# AD_0.net
KiCad netlist of a schematic drawn in Altium Designer
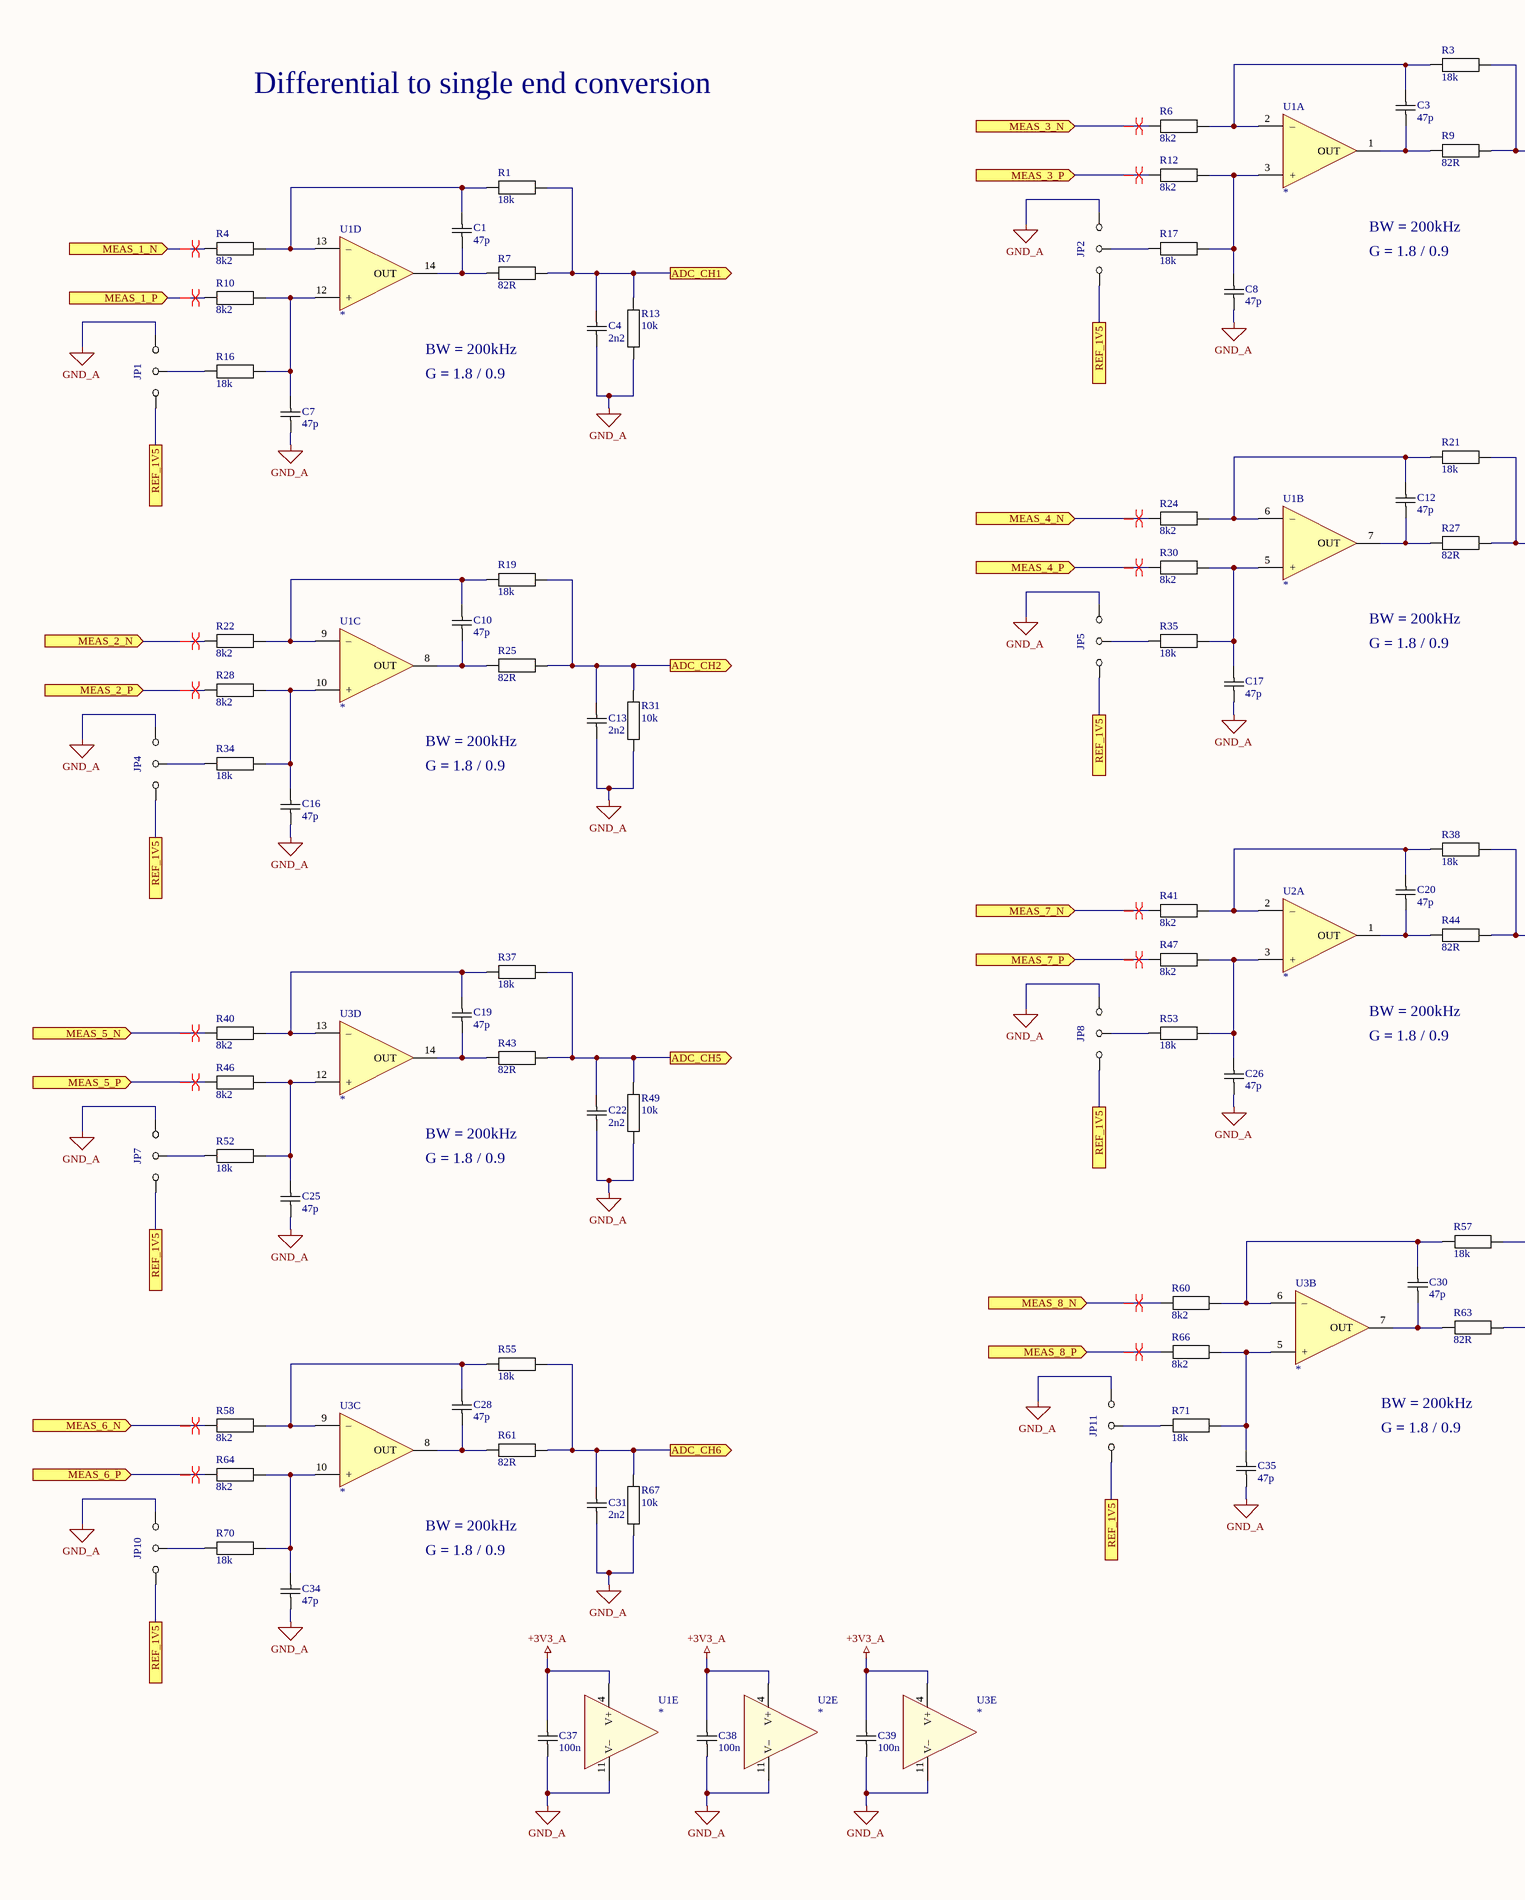
[diagram p0: AD_0.SchDoc, left]
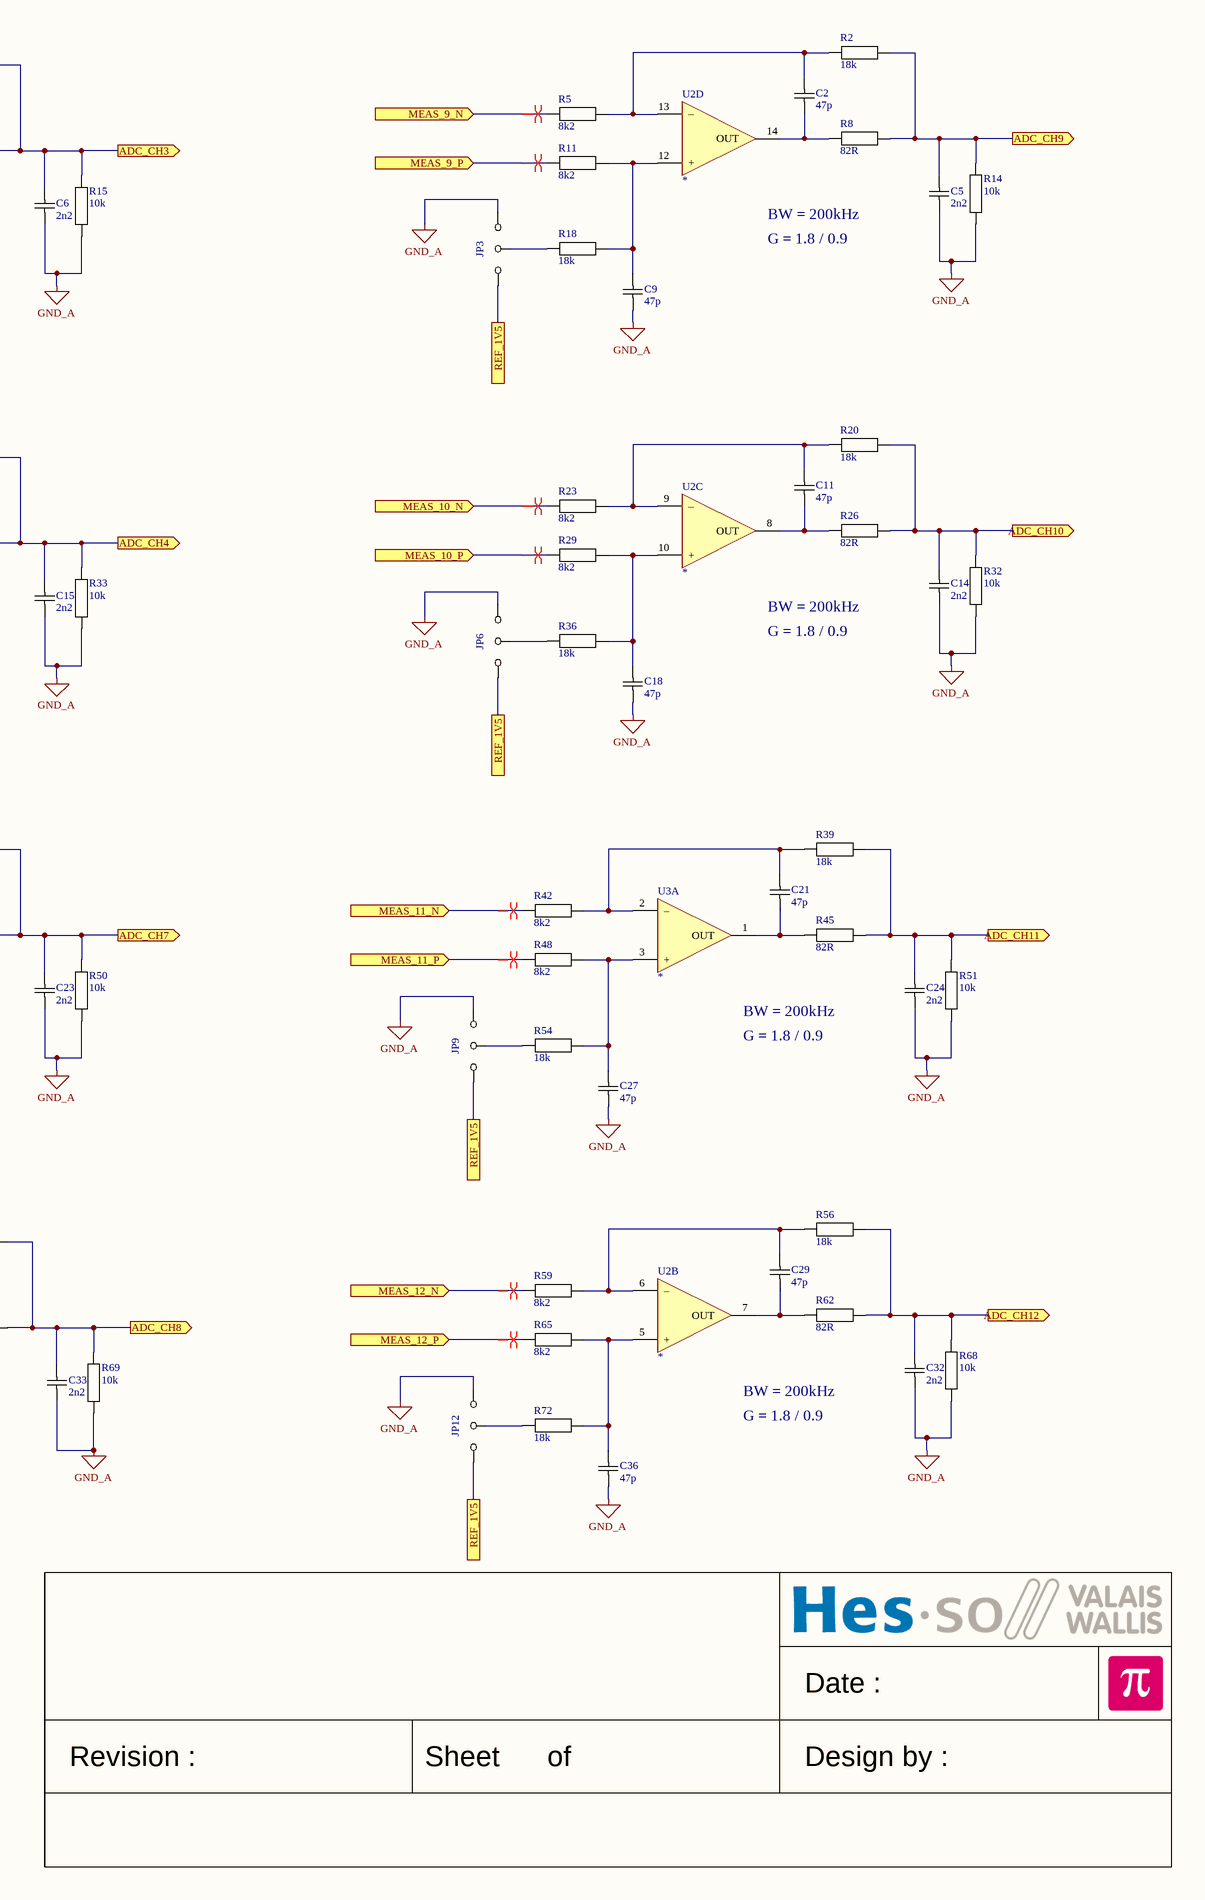
[diagram p1: AD_0.SchDoc, right]

(export (version "E")
  (design (tool "Eeschema 10.0.6"))
  (components
    (comp (ref "C1")
      (value "47p")
      (footprint "CAPACITOR 1608 REFLOW")
      (description "Capacitor X7R 10% 50V 1608(0603)")
      (libsource (lib "Capacitor") (part "Capacitor"))
    )
    (comp (ref "C2")
      (value "47p")
      (footprint "CAPACITOR 1608 REFLOW")
      (description "Capacitor X7R 10% 50V 1608(0603)")
      (libsource (lib "Capacitor") (part "Capacitor"))
    )
    (comp (ref "C3")
      (value "47p")
      (footprint "CAPACITOR 1608 REFLOW")
      (description "Capacitor X7R 10% 50V 1608(0603)")
      (libsource (lib "Capacitor") (part "Capacitor"))
    )
    (comp (ref "C4")
      (value "2n2")
      (footprint "CAPACITOR 1608 REFLOW")
      (description "Capacitor X7R 10% 50V 1608(0603)")
      (libsource (lib "Capacitor") (part "Capacitor"))
    )
    (comp (ref "C5")
      (value "2n2")
      (footprint "CAPACITOR 1608 REFLOW")
      (description "Capacitor X7R 10% 50V 1608(0603)")
      (libsource (lib "Capacitor") (part "Capacitor"))
    )
    (comp (ref "C6")
      (value "2n2")
      (footprint "CAPACITOR 1608 REFLOW")
      (description "Capacitor X7R 10% 50V 1608(0603)")
      (libsource (lib "Capacitor") (part "Capacitor"))
    )
    (comp (ref "C7")
      (value "47p")
      (footprint "CAPACITOR 1608 REFLOW")
      (description "Capacitor X7R 10% 50V 1608(0603)")
      (libsource (lib "Capacitor") (part "Capacitor"))
    )
    (comp (ref "C8")
      (value "47p")
      (footprint "CAPACITOR 1608 REFLOW")
      (description "Capacitor X7R 10% 50V 1608(0603)")
      (libsource (lib "Capacitor") (part "Capacitor"))
    )
    (comp (ref "C9")
      (value "47p")
      (footprint "CAPACITOR 1608 REFLOW")
      (description "Capacitor X7R 10% 50V 1608(0603)")
      (libsource (lib "Capacitor") (part "Capacitor"))
    )
    (comp (ref "C10")
      (value "47p")
      (footprint "CAPACITOR 1608 REFLOW")
      (description "Capacitor X7R 10% 50V 1608(0603)")
      (libsource (lib "Capacitor") (part "Capacitor"))
    )
    (comp (ref "C11")
      (value "47p")
      (footprint "CAPACITOR 1608 REFLOW")
      (description "Capacitor X7R 10% 50V 1608(0603)")
      (libsource (lib "Capacitor") (part "Capacitor"))
    )
    (comp (ref "C12")
      (value "47p")
      (footprint "CAPACITOR 1608 REFLOW")
      (description "Capacitor X7R 10% 50V 1608(0603)")
      (libsource (lib "Capacitor") (part "Capacitor"))
    )
    (comp (ref "C13")
      (value "2n2")
      (footprint "CAPACITOR 1608 REFLOW")
      (description "Capacitor X7R 10% 50V 1608(0603)")
      (libsource (lib "Capacitor") (part "Capacitor"))
    )
    (comp (ref "C14")
      (value "2n2")
      (footprint "CAPACITOR 1608 REFLOW")
      (description "Capacitor X7R 10% 50V 1608(0603)")
      (libsource (lib "Capacitor") (part "Capacitor"))
    )
    (comp (ref "C15")
      (value "2n2")
      (footprint "CAPACITOR 1608 REFLOW")
      (description "Capacitor X7R 10% 50V 1608(0603)")
      (libsource (lib "Capacitor") (part "Capacitor"))
    )
    (comp (ref "C16")
      (value "47p")
      (footprint "CAPACITOR 1608 REFLOW")
      (description "Capacitor X7R 10% 50V 1608(0603)")
      (libsource (lib "Capacitor") (part "Capacitor"))
    )
    (comp (ref "C17")
      (value "47p")
      (footprint "CAPACITOR 1608 REFLOW")
      (description "Capacitor X7R 10% 50V 1608(0603)")
      (libsource (lib "Capacitor") (part "Capacitor"))
    )
    (comp (ref "C18")
      (value "47p")
      (footprint "CAPACITOR 1608 REFLOW")
      (description "Capacitor X7R 10% 50V 1608(0603)")
      (libsource (lib "Capacitor") (part "Capacitor"))
    )
    (comp (ref "C19")
      (value "47p")
      (footprint "CAPACITOR 1608 REFLOW")
      (description "Capacitor X7R 10% 50V 1608(0603)")
      (libsource (lib "Capacitor") (part "Capacitor"))
    )
    (comp (ref "C20")
      (value "47p")
      (footprint "CAPACITOR 1608 REFLOW")
      (description "Capacitor X7R 10% 50V 1608(0603)")
      (libsource (lib "Capacitor") (part "Capacitor"))
    )
    (comp (ref "C21")
      (value "47p")
      (footprint "CAPACITOR 1608 REFLOW")
      (description "Capacitor X7R 10% 50V 1608(0603)")
      (libsource (lib "Capacitor") (part "Capacitor"))
    )
    (comp (ref "C22")
      (value "2n2")
      (footprint "CAPACITOR 1608 REFLOW")
      (description "Capacitor X7R 10% 50V 1608(0603)")
      (libsource (lib "Capacitor") (part "Capacitor"))
    )
    (comp (ref "C23")
      (value "2n2")
      (footprint "CAPACITOR 1608 REFLOW")
      (description "Capacitor X7R 10% 50V 1608(0603)")
      (libsource (lib "Capacitor") (part "Capacitor"))
    )
    (comp (ref "C24")
      (value "2n2")
      (footprint "CAPACITOR 1608 REFLOW")
      (description "Capacitor X7R 10% 50V 1608(0603)")
      (libsource (lib "Capacitor") (part "Capacitor"))
    )
    (comp (ref "C25")
      (value "47p")
      (footprint "CAPACITOR 1608 REFLOW")
      (description "Capacitor X7R 10% 50V 1608(0603)")
      (libsource (lib "Capacitor") (part "Capacitor"))
    )
    (comp (ref "C26")
      (value "47p")
      (footprint "CAPACITOR 1608 REFLOW")
      (description "Capacitor X7R 10% 50V 1608(0603)")
      (libsource (lib "Capacitor") (part "Capacitor"))
    )
    (comp (ref "C27")
      (value "47p")
      (footprint "CAPACITOR 1608 REFLOW")
      (description "Capacitor X7R 10% 50V 1608(0603)")
      (libsource (lib "Capacitor") (part "Capacitor"))
    )
    (comp (ref "C28")
      (value "47p")
      (footprint "CAPACITOR 1608 REFLOW")
      (description "Capacitor X7R 10% 50V 1608(0603)")
      (libsource (lib "Capacitor") (part "Capacitor"))
    )
    (comp (ref "C29")
      (value "47p")
      (footprint "CAPACITOR 1608 REFLOW")
      (description "Capacitor X7R 10% 50V 1608(0603)")
      (libsource (lib "Capacitor") (part "Capacitor"))
    )
    (comp (ref "C30")
      (value "47p")
      (footprint "CAPACITOR 1608 REFLOW")
      (description "Capacitor X7R 10% 50V 1608(0603)")
      (libsource (lib "Capacitor") (part "Capacitor"))
    )
    (comp (ref "C31")
      (value "2n2")
      (footprint "CAPACITOR 1608 REFLOW")
      (description "Capacitor X7R 10% 50V 1608(0603)")
      (libsource (lib "Capacitor") (part "Capacitor"))
    )
    (comp (ref "C32")
      (value "2n2")
      (footprint "CAPACITOR 1608 REFLOW")
      (description "Capacitor X7R 10% 50V 1608(0603)")
      (libsource (lib "Capacitor") (part "Capacitor"))
    )
    (comp (ref "C33")
      (value "2n2")
      (footprint "CAPACITOR 1608 REFLOW")
      (description "Capacitor X7R 10% 50V 1608(0603)")
      (libsource (lib "Capacitor") (part "Capacitor"))
    )
    (comp (ref "C34")
      (value "47p")
      (footprint "CAPACITOR 1608 REFLOW")
      (description "Capacitor X7R 10% 50V 1608(0603)")
      (libsource (lib "Capacitor") (part "Capacitor"))
    )
    (comp (ref "C35")
      (value "47p")
      (footprint "CAPACITOR 1608 REFLOW")
      (description "Capacitor X7R 10% 50V 1608(0603)")
      (libsource (lib "Capacitor") (part "Capacitor"))
    )
    (comp (ref "C36")
      (value "47p")
      (footprint "CAPACITOR 1608 REFLOW")
      (description "Capacitor X7R 10% 50V 1608(0603)")
      (libsource (lib "Capacitor") (part "Capacitor"))
    )
    (comp (ref "C37")
      (value "100n")
      (footprint "CAPACITOR 1608 REFLOW")
      (description "Capacitor X7R 10% 50V 1608(0603)")
      (libsource (lib "Capacitor") (part "Capacitor"))
    )
    (comp (ref "C38")
      (value "100n")
      (footprint "CAPACITOR 1608 REFLOW")
      (description "Capacitor X7R 10% 50V 1608(0603)")
      (libsource (lib "Capacitor") (part "Capacitor"))
    )
    (comp (ref "C39")
      (value "100n")
      (footprint "CAPACITOR 1608 REFLOW")
      (description "Capacitor X7R 10% 50V 1608(0603)")
      (libsource (lib "Capacitor") (part "Capacitor"))
    )
    (comp (ref "JP1")
      (value "{Value}")
      (footprint "JUMPER3 SMD 1608")
      (description "JUMPER 3 POS")
      (libsource (lib "Jumper") (part "JUMPER 3 POS"))
    )
    (comp (ref "JP2")
      (value "{Value}")
      (footprint "JUMPER3 SMD 1608")
      (description "JUMPER 3 POS")
      (libsource (lib "Jumper") (part "JUMPER 3 POS"))
    )
    (comp (ref "JP3")
      (value "{Value}")
      (footprint "JUMPER3 SMD 1608")
      (description "JUMPER 3 POS")
      (libsource (lib "Jumper") (part "JUMPER 3 POS"))
    )
    (comp (ref "JP4")
      (value "{Value}")
      (footprint "JUMPER3 SMD 1608")
      (description "JUMPER 3 POS")
      (libsource (lib "Jumper") (part "JUMPER 3 POS"))
    )
    (comp (ref "JP5")
      (value "{Value}")
      (footprint "JUMPER3 SMD 1608")
      (description "JUMPER 3 POS")
      (libsource (lib "Jumper") (part "JUMPER 3 POS"))
    )
    (comp (ref "JP6")
      (value "{Value}")
      (footprint "JUMPER3 SMD 1608")
      (description "JUMPER 3 POS")
      (libsource (lib "Jumper") (part "JUMPER 3 POS"))
    )
    (comp (ref "JP7")
      (value "{Value}")
      (footprint "JUMPER3 SMD 1608")
      (description "JUMPER 3 POS")
      (libsource (lib "Jumper") (part "JUMPER 3 POS"))
    )
    (comp (ref "JP8")
      (value "{Value}")
      (footprint "JUMPER3 SMD 1608")
      (description "JUMPER 3 POS")
      (libsource (lib "Jumper") (part "JUMPER 3 POS"))
    )
    (comp (ref "JP9")
      (value "{Value}")
      (footprint "JUMPER3 SMD 1608")
      (description "JUMPER 3 POS")
      (libsource (lib "Jumper") (part "JUMPER 3 POS"))
    )
    (comp (ref "JP10")
      (value "{Value}")
      (footprint "JUMPER3 SMD 1608")
      (description "JUMPER 3 POS")
      (libsource (lib "Jumper") (part "JUMPER 3 POS"))
    )
    (comp (ref "JP11")
      (value "{Value}")
      (footprint "JUMPER3 SMD 1608")
      (description "JUMPER 3 POS")
      (libsource (lib "Jumper") (part "JUMPER 3 POS"))
    )
    (comp (ref "JP12")
      (value "{Value}")
      (footprint "JUMPER3 SMD 1608")
      (description "JUMPER 3 POS")
      (libsource (lib "Jumper") (part "JUMPER 3 POS"))
    )
    (comp (ref "R1")
      (value "18k")
      (footprint "RESISTOR 1608 REFLOW")
      (description "Resistor 1% 50V 100mW 1608(0603)")
      (libsource (lib "Resistor") (part "Resistor"))
    )
    (comp (ref "R2")
      (value "18k")
      (footprint "RESISTOR 1608 REFLOW")
      (description "Resistor 1% 50V 100mW 1608(0603)")
      (libsource (lib "Resistor") (part "Resistor"))
    )
    (comp (ref "R3")
      (value "18k")
      (footprint "RESISTOR 1608 REFLOW")
      (description "Resistor 1% 50V 100mW 1608(0603)")
      (libsource (lib "Resistor") (part "Resistor"))
    )
    (comp (ref "R4")
      (value "8k2")
      (footprint "RESISTOR 1608 REFLOW")
      (description "Resistor 1% 50V 100mW 1608(0603)")
      (libsource (lib "Resistor") (part "Resistor"))
    )
    (comp (ref "R5")
      (value "8k2")
      (footprint "RESISTOR 1608 REFLOW")
      (description "Resistor 1% 50V 100mW 1608(0603)")
      (libsource (lib "Resistor") (part "Resistor"))
    )
    (comp (ref "R6")
      (value "8k2")
      (footprint "RESISTOR 1608 REFLOW")
      (description "Resistor 1% 50V 100mW 1608(0603)")
      (libsource (lib "Resistor") (part "Resistor"))
    )
    (comp (ref "R7")
      (value "82R")
      (footprint "RESISTOR 1608 REFLOW")
      (description "Resistor 1% 50V 100mW 1608(0603)")
      (libsource (lib "Resistor") (part "Resistor"))
    )
    (comp (ref "R8")
      (value "82R")
      (footprint "RESISTOR 1608 REFLOW")
      (description "Resistor 1% 50V 100mW 1608(0603)")
      (libsource (lib "Resistor") (part "Resistor"))
    )
    (comp (ref "R9")
      (value "82R")
      (footprint "RESISTOR 1608 REFLOW")
      (description "Resistor 1% 50V 100mW 1608(0603)")
      (libsource (lib "Resistor") (part "Resistor"))
    )
    (comp (ref "R10")
      (value "8k2")
      (footprint "RESISTOR 1608 REFLOW")
      (description "Resistor 1% 50V 100mW 1608(0603)")
      (libsource (lib "Resistor") (part "Resistor"))
    )
    (comp (ref "R11")
      (value "8k2")
      (footprint "RESISTOR 1608 REFLOW")
      (description "Resistor 1% 50V 100mW 1608(0603)")
      (libsource (lib "Resistor") (part "Resistor"))
    )
    (comp (ref "R12")
      (value "8k2")
      (footprint "RESISTOR 1608 REFLOW")
      (description "Resistor 1% 50V 100mW 1608(0603)")
      (libsource (lib "Resistor") (part "Resistor"))
    )
    (comp (ref "R13")
      (value "10k")
      (footprint "RESISTOR 1608 REFLOW")
      (description "Resistor 1% 50V 100mW 1608(0603)")
      (libsource (lib "Resistor") (part "Resistor"))
    )
    (comp (ref "R14")
      (value "10k")
      (footprint "RESISTOR 1608 REFLOW")
      (description "Resistor 1% 50V 100mW 1608(0603)")
      (libsource (lib "Resistor") (part "Resistor"))
    )
    (comp (ref "R15")
      (value "10k")
      (footprint "RESISTOR 1608 REFLOW")
      (description "Resistor 1% 50V 100mW 1608(0603)")
      (libsource (lib "Resistor") (part "Resistor"))
    )
    (comp (ref "R16")
      (value "18k")
      (footprint "RESISTOR 1608 REFLOW")
      (description "Resistor 1% 50V 100mW 1608(0603)")
      (libsource (lib "Resistor") (part "Resistor"))
    )
    (comp (ref "R17")
      (value "18k")
      (footprint "RESISTOR 1608 REFLOW")
      (description "Resistor 1% 50V 100mW 1608(0603)")
      (libsource (lib "Resistor") (part "Resistor"))
    )
    (comp (ref "R18")
      (value "18k")
      (footprint "RESISTOR 1608 REFLOW")
      (description "Resistor 1% 50V 100mW 1608(0603)")
      (libsource (lib "Resistor") (part "Resistor"))
    )
    (comp (ref "R19")
      (value "18k")
      (footprint "RESISTOR 1608 REFLOW")
      (description "Resistor 1% 50V 100mW 1608(0603)")
      (libsource (lib "Resistor") (part "Resistor"))
    )
    (comp (ref "R20")
      (value "18k")
      (footprint "RESISTOR 1608 REFLOW")
      (description "Resistor 1% 50V 100mW 1608(0603)")
      (libsource (lib "Resistor") (part "Resistor"))
    )
    (comp (ref "R21")
      (value "18k")
      (footprint "RESISTOR 1608 REFLOW")
      (description "Resistor 1% 50V 100mW 1608(0603)")
      (libsource (lib "Resistor") (part "Resistor"))
    )
    (comp (ref "R22")
      (value "8k2")
      (footprint "RESISTOR 1608 REFLOW")
      (description "Resistor 1% 50V 100mW 1608(0603)")
      (libsource (lib "Resistor") (part "Resistor"))
    )
    (comp (ref "R23")
      (value "8k2")
      (footprint "RESISTOR 1608 REFLOW")
      (description "Resistor 1% 50V 100mW 1608(0603)")
      (libsource (lib "Resistor") (part "Resistor"))
    )
    (comp (ref "R24")
      (value "8k2")
      (footprint "RESISTOR 1608 REFLOW")
      (description "Resistor 1% 50V 100mW 1608(0603)")
      (libsource (lib "Resistor") (part "Resistor"))
    )
    (comp (ref "R25")
      (value "82R")
      (footprint "RESISTOR 1608 REFLOW")
      (description "Resistor 1% 50V 100mW 1608(0603)")
      (libsource (lib "Resistor") (part "Resistor"))
    )
    (comp (ref "R26")
      (value "82R")
      (footprint "RESISTOR 1608 REFLOW")
      (description "Resistor 1% 50V 100mW 1608(0603)")
      (libsource (lib "Resistor") (part "Resistor"))
    )
    (comp (ref "R27")
      (value "82R")
      (footprint "RESISTOR 1608 REFLOW")
      (description "Resistor 1% 50V 100mW 1608(0603)")
      (libsource (lib "Resistor") (part "Resistor"))
    )
    (comp (ref "R28")
      (value "8k2")
      (footprint "RESISTOR 1608 REFLOW")
      (description "Resistor 1% 50V 100mW 1608(0603)")
      (libsource (lib "Resistor") (part "Resistor"))
    )
    (comp (ref "R29")
      (value "8k2")
      (footprint "RESISTOR 1608 REFLOW")
      (description "Resistor 1% 50V 100mW 1608(0603)")
      (libsource (lib "Resistor") (part "Resistor"))
    )
    (comp (ref "R30")
      (value "8k2")
      (footprint "RESISTOR 1608 REFLOW")
      (description "Resistor 1% 50V 100mW 1608(0603)")
      (libsource (lib "Resistor") (part "Resistor"))
    )
    (comp (ref "R31")
      (value "10k")
      (footprint "RESISTOR 1608 REFLOW")
      (description "Resistor 1% 50V 100mW 1608(0603)")
      (libsource (lib "Resistor") (part "Resistor"))
    )
    (comp (ref "R32")
      (value "10k")
      (footprint "RESISTOR 1608 REFLOW")
      (description "Resistor 1% 50V 100mW 1608(0603)")
      (libsource (lib "Resistor") (part "Resistor"))
    )
    (comp (ref "R33")
      (value "10k")
      (footprint "RESISTOR 1608 REFLOW")
      (description "Resistor 1% 50V 100mW 1608(0603)")
      (libsource (lib "Resistor") (part "Resistor"))
    )
    (comp (ref "R34")
      (value "18k")
      (footprint "RESISTOR 1608 REFLOW")
      (description "Resistor 1% 50V 100mW 1608(0603)")
      (libsource (lib "Resistor") (part "Resistor"))
    )
    (comp (ref "R35")
      (value "18k")
      (footprint "RESISTOR 1608 REFLOW")
      (description "Resistor 1% 50V 100mW 1608(0603)")
      (libsource (lib "Resistor") (part "Resistor"))
    )
    (comp (ref "R36")
      (value "18k")
      (footprint "RESISTOR 1608 REFLOW")
      (description "Resistor 1% 50V 100mW 1608(0603)")
      (libsource (lib "Resistor") (part "Resistor"))
    )
    (comp (ref "R37")
      (value "18k")
      (footprint "RESISTOR 1608 REFLOW")
      (description "Resistor 1% 50V 100mW 1608(0603)")
      (libsource (lib "Resistor") (part "Resistor"))
    )
    (comp (ref "R38")
      (value "18k")
      (footprint "RESISTOR 1608 REFLOW")
      (description "Resistor 1% 50V 100mW 1608(0603)")
      (libsource (lib "Resistor") (part "Resistor"))
    )
    (comp (ref "R39")
      (value "18k")
      (footprint "RESISTOR 1608 REFLOW")
      (description "Resistor 1% 50V 100mW 1608(0603)")
      (libsource (lib "Resistor") (part "Resistor"))
    )
    (comp (ref "R40")
      (value "8k2")
      (footprint "RESISTOR 1608 REFLOW")
      (description "Resistor 1% 50V 100mW 1608(0603)")
      (libsource (lib "Resistor") (part "Resistor"))
    )
    (comp (ref "R41")
      (value "8k2")
      (footprint "RESISTOR 1608 REFLOW")
      (description "Resistor 1% 50V 100mW 1608(0603)")
      (libsource (lib "Resistor") (part "Resistor"))
    )
    (comp (ref "R42")
      (value "8k2")
      (footprint "RESISTOR 1608 REFLOW")
      (description "Resistor 1% 50V 100mW 1608(0603)")
      (libsource (lib "Resistor") (part "Resistor"))
    )
    (comp (ref "R43")
      (value "82R")
      (footprint "RESISTOR 1608 REFLOW")
      (description "Resistor 1% 50V 100mW 1608(0603)")
      (libsource (lib "Resistor") (part "Resistor"))
    )
    (comp (ref "R44")
      (value "82R")
      (footprint "RESISTOR 1608 REFLOW")
      (description "Resistor 1% 50V 100mW 1608(0603)")
      (libsource (lib "Resistor") (part "Resistor"))
    )
    (comp (ref "R45")
      (value "82R")
      (footprint "RESISTOR 1608 REFLOW")
      (description "Resistor 1% 50V 100mW 1608(0603)")
      (libsource (lib "Resistor") (part "Resistor"))
    )
    (comp (ref "R46")
      (value "8k2")
      (footprint "RESISTOR 1608 REFLOW")
      (description "Resistor 1% 50V 100mW 1608(0603)")
      (libsource (lib "Resistor") (part "Resistor"))
    )
    (comp (ref "R47")
      (value "8k2")
      (footprint "RESISTOR 1608 REFLOW")
      (description "Resistor 1% 50V 100mW 1608(0603)")
      (libsource (lib "Resistor") (part "Resistor"))
    )
    (comp (ref "R48")
      (value "8k2")
      (footprint "RESISTOR 1608 REFLOW")
      (description "Resistor 1% 50V 100mW 1608(0603)")
      (libsource (lib "Resistor") (part "Resistor"))
    )
    (comp (ref "R49")
      (value "10k")
      (footprint "RESISTOR 1608 REFLOW")
      (description "Resistor 1% 50V 100mW 1608(0603)")
      (libsource (lib "Resistor") (part "Resistor"))
    )
    (comp (ref "R50")
      (value "10k")
      (footprint "RESISTOR 1608 REFLOW")
      (description "Resistor 1% 50V 100mW 1608(0603)")
      (libsource (lib "Resistor") (part "Resistor"))
    )
    (comp (ref "R51")
      (value "10k")
      (footprint "RESISTOR 1608 REFLOW")
      (description "Resistor 1% 50V 100mW 1608(0603)")
      (libsource (lib "Resistor") (part "Resistor"))
    )
    (comp (ref "R52")
      (value "18k")
      (footprint "RESISTOR 1608 REFLOW")
      (description "Resistor 1% 50V 100mW 1608(0603)")
      (libsource (lib "Resistor") (part "Resistor"))
    )
    (comp (ref "R53")
      (value "18k")
      (footprint "RESISTOR 1608 REFLOW")
      (description "Resistor 1% 50V 100mW 1608(0603)")
      (libsource (lib "Resistor") (part "Resistor"))
    )
    (comp (ref "R54")
      (value "18k")
      (footprint "RESISTOR 1608 REFLOW")
      (description "Resistor 1% 50V 100mW 1608(0603)")
      (libsource (lib "Resistor") (part "Resistor"))
    )
    (comp (ref "R55")
      (value "18k")
      (footprint "RESISTOR 1608 REFLOW")
      (description "Resistor 1% 50V 100mW 1608(0603)")
      (libsource (lib "Resistor") (part "Resistor"))
    )
    (comp (ref "R56")
      (value "18k")
      (footprint "RESISTOR 1608 REFLOW")
      (description "Resistor 1% 50V 100mW 1608(0603)")
      (libsource (lib "Resistor") (part "Resistor"))
    )
    (comp (ref "R57")
      (value "18k")
      (footprint "RESISTOR 1608 REFLOW")
      (description "Resistor 1% 50V 100mW 1608(0603)")
      (libsource (lib "Resistor") (part "Resistor"))
    )
    (comp (ref "R58")
      (value "8k2")
      (footprint "RESISTOR 1608 REFLOW")
      (description "Resistor 1% 50V 100mW 1608(0603)")
      (libsource (lib "Resistor") (part "Resistor"))
    )
    (comp (ref "R59")
      (value "8k2")
      (footprint "RESISTOR 1608 REFLOW")
      (description "Resistor 1% 50V 100mW 1608(0603)")
      (libsource (lib "Resistor") (part "Resistor"))
    )
    (comp (ref "R60")
      (value "8k2")
      (footprint "RESISTOR 1608 REFLOW")
      (description "Resistor 1% 50V 100mW 1608(0603)")
      (libsource (lib "Resistor") (part "Resistor"))
    )
    (comp (ref "R61")
      (value "82R")
      (footprint "RESISTOR 1608 REFLOW")
      (description "Resistor 1% 50V 100mW 1608(0603)")
      (libsource (lib "Resistor") (part "Resistor"))
    )
    (comp (ref "R62")
      (value "82R")
      (footprint "RESISTOR 1608 REFLOW")
      (description "Resistor 1% 50V 100mW 1608(0603)")
      (libsource (lib "Resistor") (part "Resistor"))
    )
    (comp (ref "R63")
      (value "82R")
      (footprint "RESISTOR 1608 REFLOW")
      (description "Resistor 1% 50V 100mW 1608(0603)")
      (libsource (lib "Resistor") (part "Resistor"))
    )
    (comp (ref "R64")
      (value "8k2")
      (footprint "RESISTOR 1608 REFLOW")
      (description "Resistor 1% 50V 100mW 1608(0603)")
      (libsource (lib "Resistor") (part "Resistor"))
    )
    (comp (ref "R65")
      (value "8k2")
      (footprint "RESISTOR 1608 REFLOW")
      (description "Resistor 1% 50V 100mW 1608(0603)")
      (libsource (lib "Resistor") (part "Resistor"))
    )
    (comp (ref "R66")
      (value "8k2")
      (footprint "RESISTOR 1608 REFLOW")
      (description "Resistor 1% 50V 100mW 1608(0603)")
      (libsource (lib "Resistor") (part "Resistor"))
    )
    (comp (ref "R67")
      (value "10k")
      (footprint "RESISTOR 1608 REFLOW")
      (description "Resistor 1% 50V 100mW 1608(0603)")
      (libsource (lib "Resistor") (part "Resistor"))
    )
    (comp (ref "R68")
      (value "10k")
      (footprint "RESISTOR 1608 REFLOW")
      (description "Resistor 1% 50V 100mW 1608(0603)")
      (libsource (lib "Resistor") (part "Resistor"))
    )
    (comp (ref "R69")
      (value "10k")
      (footprint "RESISTOR 1608 REFLOW")
      (description "Resistor 1% 50V 100mW 1608(0603)")
      (libsource (lib "Resistor") (part "Resistor"))
    )
    (comp (ref "R70")
      (value "18k")
      (footprint "RESISTOR 1608 REFLOW")
      (description "Resistor 1% 50V 100mW 1608(0603)")
      (libsource (lib "Resistor") (part "Resistor"))
    )
    (comp (ref "R71")
      (value "18k")
      (footprint "RESISTOR 1608 REFLOW")
      (description "Resistor 1% 50V 100mW 1608(0603)")
      (libsource (lib "Resistor") (part "Resistor"))
    )
    (comp (ref "R72")
      (value "18k")
      (footprint "RESISTOR 1608 REFLOW")
      (description "Resistor 1% 50V 100mW 1608(0603)")
      (libsource (lib "Resistor") (part "Resistor"))
    )
    (comp (ref "U1")
      (value "*")
      (footprint "SO14 P1.27 C4.0X8.8 H1.75")
      (description "Generic quad OPA 14 pins")
      (libsource (lib "Amplifier") (part "OPA QUAD"))
    )
    (comp (ref "U2")
      (value "*")
      (footprint "SO14 P1.27 C4.0X8.8 H1.75")
      (description "Generic quad OPA 14 pins")
      (libsource (lib "Amplifier") (part "OPA QUAD"))
    )
    (comp (ref "U3")
      (value "*")
      (footprint "SO14 P1.27 C4.0X8.8 H1.75")
      (description "Generic quad OPA 14 pins")
      (libsource (lib "Amplifier") (part "OPA QUAD"))
    )
  )
  (nets
    (net (code "1") (name "+3V3_A") (class "Default")
      (node (ref "C37") (pin "2") (pinfunction "2_2") (pintype "passive"))
      (node (ref "C38") (pin "2") (pinfunction "2_2") (pintype "passive"))
      (node (ref "C39") (pin "2") (pinfunction "2_2") (pintype "passive"))
      (node (ref "U1") (pin "4") (pinfunction "V+_4") (pintype "passive"))
      (node (ref "U2") (pin "4") (pinfunction "V+_4") (pintype "passive"))
      (node (ref "U3") (pin "4") (pinfunction "V+_4") (pintype "passive"))
    )
    (net (code "2") (name "/ADC_CH1") (class "Default")
      (node (ref "C4") (pin "2") (pinfunction "2_2") (pintype "passive"))
      (node (ref "R1") (pin "2") (pinfunction "2_2") (pintype "passive"))
      (node (ref "R13") (pin "1") (pinfunction "1_1") (pintype "passive"))
      (node (ref "R7") (pin "2") (pinfunction "2_2") (pintype "passive"))
    )
    (net (code "3") (name "/ADC_CH2") (class "Default")
      (node (ref "C13") (pin "2") (pinfunction "2_2") (pintype "passive"))
      (node (ref "R19") (pin "2") (pinfunction "2_2") (pintype "passive"))
      (node (ref "R25") (pin "2") (pinfunction "2_2") (pintype "passive"))
      (node (ref "R31") (pin "1") (pinfunction "1_1") (pintype "passive"))
    )
    (net (code "4") (name "/ADC_CH3") (class "Default")
      (node (ref "C6") (pin "2") (pinfunction "2_2") (pintype "passive"))
      (node (ref "R15") (pin "1") (pinfunction "1_1") (pintype "passive"))
      (node (ref "R3") (pin "2") (pinfunction "2_2") (pintype "passive"))
      (node (ref "R9") (pin "2") (pinfunction "2_2") (pintype "passive"))
    )
    (net (code "5") (name "/ADC_CH4") (class "Default")
      (node (ref "C15") (pin "2") (pinfunction "2_2") (pintype "passive"))
      (node (ref "R21") (pin "2") (pinfunction "2_2") (pintype "passive"))
      (node (ref "R27") (pin "2") (pinfunction "2_2") (pintype "passive"))
      (node (ref "R33") (pin "1") (pinfunction "1_1") (pintype "passive"))
    )
    (net (code "6") (name "/ADC_CH5") (class "Default")
      (node (ref "C22") (pin "2") (pinfunction "2_2") (pintype "passive"))
      (node (ref "R37") (pin "2") (pinfunction "2_2") (pintype "passive"))
      (node (ref "R43") (pin "2") (pinfunction "2_2") (pintype "passive"))
      (node (ref "R49") (pin "1") (pinfunction "1_1") (pintype "passive"))
    )
    (net (code "7") (name "/ADC_CH6") (class "Default")
      (node (ref "C31") (pin "2") (pinfunction "2_2") (pintype "passive"))
      (node (ref "R55") (pin "2") (pinfunction "2_2") (pintype "passive"))
      (node (ref "R61") (pin "2") (pinfunction "2_2") (pintype "passive"))
      (node (ref "R67") (pin "1") (pinfunction "1_1") (pintype "passive"))
    )
    (net (code "8") (name "/ADC_CH7") (class "Default")
      (node (ref "C23") (pin "2") (pinfunction "2_2") (pintype "passive"))
      (node (ref "R38") (pin "2") (pinfunction "2_2") (pintype "passive"))
      (node (ref "R44") (pin "2") (pinfunction "2_2") (pintype "passive"))
      (node (ref "R50") (pin "1") (pinfunction "1_1") (pintype "passive"))
    )
    (net (code "9") (name "/ADC_CH8") (class "Default")
      (node (ref "C33") (pin "2") (pinfunction "2_2") (pintype "passive"))
      (node (ref "R57") (pin "2") (pinfunction "2_2") (pintype "passive"))
      (node (ref "R63") (pin "2") (pinfunction "2_2") (pintype "passive"))
      (node (ref "R69") (pin "1") (pinfunction "1_1") (pintype "passive"))
    )
    (net (code "10") (name "/ADC_CH9") (class "Default")
      (node (ref "C5") (pin "2") (pinfunction "2_2") (pintype "passive"))
      (node (ref "R14") (pin "1") (pinfunction "1_1") (pintype "passive"))
      (node (ref "R2") (pin "2") (pinfunction "2_2") (pintype "passive"))
      (node (ref "R8") (pin "2") (pinfunction "2_2") (pintype "passive"))
    )
    (net (code "11") (name "/ADC_CH10") (class "Default")
      (node (ref "C14") (pin "2") (pinfunction "2_2") (pintype "passive"))
      (node (ref "R20") (pin "2") (pinfunction "2_2") (pintype "passive"))
      (node (ref "R26") (pin "2") (pinfunction "2_2") (pintype "passive"))
      (node (ref "R32") (pin "1") (pinfunction "1_1") (pintype "passive"))
    )
    (net (code "12") (name "/ADC_CH11") (class "Default")
      (node (ref "C24") (pin "2") (pinfunction "2_2") (pintype "passive"))
      (node (ref "R39") (pin "2") (pinfunction "2_2") (pintype "passive"))
      (node (ref "R45") (pin "2") (pinfunction "2_2") (pintype "passive"))
      (node (ref "R51") (pin "1") (pinfunction "1_1") (pintype "passive"))
    )
    (net (code "13") (name "/ADC_CH12") (class "Default")
      (node (ref "C32") (pin "2") (pinfunction "2_2") (pintype "passive"))
      (node (ref "R56") (pin "2") (pinfunction "2_2") (pintype "passive"))
      (node (ref "R62") (pin "2") (pinfunction "2_2") (pintype "passive"))
      (node (ref "R68") (pin "1") (pinfunction "1_1") (pintype "passive"))
    )
    (net (code "14") (name "/MEAS_1_N") (class "Default")
      (node (ref "R4") (pin "1") (pinfunction "1_1") (pintype "passive"))
    )
    (net (code "15") (name "/MEAS_1_P") (class "Default")
      (node (ref "R10") (pin "1") (pinfunction "1_1") (pintype "passive"))
    )
    (net (code "16") (name "/MEAS_2_N") (class "Default")
      (node (ref "R22") (pin "1") (pinfunction "1_1") (pintype "passive"))
    )
    (net (code "17") (name "/MEAS_2_P") (class "Default")
      (node (ref "R28") (pin "1") (pinfunction "1_1") (pintype "passive"))
    )
    (net (code "18") (name "/MEAS_3_N") (class "Default")
      (node (ref "R6") (pin "1") (pinfunction "1_1") (pintype "passive"))
    )
    (net (code "19") (name "/MEAS_3_P") (class "Default")
      (node (ref "R12") (pin "1") (pinfunction "1_1") (pintype "passive"))
    )
    (net (code "20") (name "/MEAS_4_N") (class "Default")
      (node (ref "R24") (pin "1") (pinfunction "1_1") (pintype "passive"))
    )
    (net (code "21") (name "/MEAS_4_P") (class "Default")
      (node (ref "R30") (pin "1") (pinfunction "1_1") (pintype "passive"))
    )
    (net (code "22") (name "/MEAS_5_N") (class "Default")
      (node (ref "R40") (pin "1") (pinfunction "1_1") (pintype "passive"))
    )
    (net (code "23") (name "/MEAS_5_P") (class "Default")
      (node (ref "R46") (pin "1") (pinfunction "1_1") (pintype "passive"))
    )
    (net (code "24") (name "/MEAS_6_N") (class "Default")
      (node (ref "R58") (pin "1") (pinfunction "1_1") (pintype "passive"))
    )
    (net (code "25") (name "/MEAS_6_P") (class "Default")
      (node (ref "R64") (pin "1") (pinfunction "1_1") (pintype "passive"))
    )
    (net (code "26") (name "/MEAS_7_N") (class "Default")
      (node (ref "R41") (pin "1") (pinfunction "1_1") (pintype "passive"))
    )
    (net (code "27") (name "/MEAS_7_P") (class "Default")
      (node (ref "R47") (pin "1") (pinfunction "1_1") (pintype "passive"))
    )
    (net (code "28") (name "/MEAS_8_N") (class "Default")
      (node (ref "R60") (pin "1") (pinfunction "1_1") (pintype "passive"))
    )
    (net (code "29") (name "/MEAS_8_P") (class "Default")
      (node (ref "R66") (pin "1") (pinfunction "1_1") (pintype "passive"))
    )
    (net (code "30") (name "/MEAS_9_N") (class "Default")
      (node (ref "R5") (pin "1") (pinfunction "1_1") (pintype "passive"))
    )
    (net (code "31") (name "/MEAS_9_P") (class "Default")
      (node (ref "R11") (pin "1") (pinfunction "1_1") (pintype "passive"))
    )
    (net (code "32") (name "/MEAS_10_N") (class "Default")
      (node (ref "R23") (pin "1") (pinfunction "1_1") (pintype "passive"))
    )
    (net (code "33") (name "/MEAS_10_P") (class "Default")
      (node (ref "R29") (pin "1") (pinfunction "1_1") (pintype "passive"))
    )
    (net (code "34") (name "/MEAS_11_N") (class "Default")
      (node (ref "R42") (pin "1") (pinfunction "1_1") (pintype "passive"))
    )
    (net (code "35") (name "/MEAS_11_P") (class "Default")
      (node (ref "R48") (pin "1") (pinfunction "1_1") (pintype "passive"))
    )
    (net (code "36") (name "/MEAS_12_N") (class "Default")
      (node (ref "R59") (pin "1") (pinfunction "1_1") (pintype "passive"))
    )
    (net (code "37") (name "/MEAS_12_P") (class "Default")
      (node (ref "R65") (pin "1") (pinfunction "1_1") (pintype "passive"))
    )
    (net (code "38") (name "/REF_1V5") (class "Default")
      (node (ref "JP1") (pin "1") (pinfunction "1_1") (pintype "passive"))
      (node (ref "JP10") (pin "1") (pinfunction "1_1") (pintype "passive"))
      (node (ref "JP11") (pin "1") (pinfunction "1_1") (pintype "passive"))
      (node (ref "JP12") (pin "1") (pinfunction "1_1") (pintype "passive"))
      (node (ref "JP2") (pin "1") (pinfunction "1_1") (pintype "passive"))
      (node (ref "JP3") (pin "1") (pinfunction "1_1") (pintype "passive"))
      (node (ref "JP4") (pin "1") (pinfunction "1_1") (pintype "passive"))
      (node (ref "JP5") (pin "1") (pinfunction "1_1") (pintype "passive"))
      (node (ref "JP6") (pin "1") (pinfunction "1_1") (pintype "passive"))
      (node (ref "JP7") (pin "1") (pinfunction "1_1") (pintype "passive"))
      (node (ref "JP8") (pin "1") (pinfunction "1_1") (pintype "passive"))
      (node (ref "JP9") (pin "1") (pinfunction "1_1") (pintype "passive"))
    )
    (net (code "39") (name "GND_A") (class "Default")
      (node (ref "C13") (pin "1") (pinfunction "1_1") (pintype "passive"))
      (node (ref "C14") (pin "1") (pinfunction "1_1") (pintype "passive"))
      (node (ref "C15") (pin "1") (pinfunction "1_1") (pintype "passive"))
      (node (ref "C16") (pin "1") (pinfunction "1_1") (pintype "passive"))
      (node (ref "C17") (pin "1") (pinfunction "1_1") (pintype "passive"))
      (node (ref "C18") (pin "1") (pinfunction "1_1") (pintype "passive"))
      (node (ref "C22") (pin "1") (pinfunction "1_1") (pintype "passive"))
      (node (ref "C23") (pin "1") (pinfunction "1_1") (pintype "passive"))
      (node (ref "C24") (pin "1") (pinfunction "1_1") (pintype "passive"))
      (node (ref "C25") (pin "1") (pinfunction "1_1") (pintype "passive"))
      (node (ref "C26") (pin "1") (pinfunction "1_1") (pintype "passive"))
      (node (ref "C27") (pin "1") (pinfunction "1_1") (pintype "passive"))
      (node (ref "C31") (pin "1") (pinfunction "1_1") (pintype "passive"))
      (node (ref "C32") (pin "1") (pinfunction "1_1") (pintype "passive"))
      (node (ref "C33") (pin "1") (pinfunction "1_1") (pintype "passive"))
      (node (ref "C34") (pin "1") (pinfunction "1_1") (pintype "passive"))
      (node (ref "C35") (pin "1") (pinfunction "1_1") (pintype "passive"))
      (node (ref "C36") (pin "1") (pinfunction "1_1") (pintype "passive"))
      (node (ref "C37") (pin "1") (pinfunction "1_1") (pintype "passive"))
      (node (ref "C38") (pin "1") (pinfunction "1_1") (pintype "passive"))
      (node (ref "C39") (pin "1") (pinfunction "1_1") (pintype "passive"))
      (node (ref "C4") (pin "1") (pinfunction "1_1") (pintype "passive"))
      (node (ref "C5") (pin "1") (pinfunction "1_1") (pintype "passive"))
      (node (ref "C6") (pin "1") (pinfunction "1_1") (pintype "passive"))
      (node (ref "C7") (pin "1") (pinfunction "1_1") (pintype "passive"))
      (node (ref "C8") (pin "1") (pinfunction "1_1") (pintype "passive"))
      (node (ref "C9") (pin "1") (pinfunction "1_1") (pintype "passive"))
      (node (ref "JP1") (pin "3") (pinfunction "3_3") (pintype "passive"))
      (node (ref "JP10") (pin "3") (pinfunction "3_3") (pintype "passive"))
      (node (ref "JP11") (pin "3") (pinfunction "3_3") (pintype "passive"))
      (node (ref "JP12") (pin "3") (pinfunction "3_3") (pintype "passive"))
      (node (ref "JP2") (pin "3") (pinfunction "3_3") (pintype "passive"))
      (node (ref "JP3") (pin "3") (pinfunction "3_3") (pintype "passive"))
      (node (ref "JP4") (pin "3") (pinfunction "3_3") (pintype "passive"))
      (node (ref "JP5") (pin "3") (pinfunction "3_3") (pintype "passive"))
      (node (ref "JP6") (pin "3") (pinfunction "3_3") (pintype "passive"))
      (node (ref "JP7") (pin "3") (pinfunction "3_3") (pintype "passive"))
      (node (ref "JP8") (pin "3") (pinfunction "3_3") (pintype "passive"))
      (node (ref "JP9") (pin "3") (pinfunction "3_3") (pintype "passive"))
      (node (ref "R13") (pin "2") (pinfunction "2_2") (pintype "passive"))
      (node (ref "R14") (pin "2") (pinfunction "2_2") (pintype "passive"))
      (node (ref "R15") (pin "2") (pinfunction "2_2") (pintype "passive"))
      (node (ref "R31") (pin "2") (pinfunction "2_2") (pintype "passive"))
      (node (ref "R32") (pin "2") (pinfunction "2_2") (pintype "passive"))
      (node (ref "R33") (pin "2") (pinfunction "2_2") (pintype "passive"))
      (node (ref "R49") (pin "2") (pinfunction "2_2") (pintype "passive"))
      (node (ref "R50") (pin "2") (pinfunction "2_2") (pintype "passive"))
      (node (ref "R51") (pin "2") (pinfunction "2_2") (pintype "passive"))
      (node (ref "R67") (pin "2") (pinfunction "2_2") (pintype "passive"))
      (node (ref "R68") (pin "2") (pinfunction "2_2") (pintype "passive"))
      (node (ref "R69") (pin "2") (pinfunction "2_2") (pintype "passive"))
      (node (ref "U1") (pin "11") (pinfunction "V–_11") (pintype "passive"))
      (node (ref "U2") (pin "11") (pinfunction "V–_11") (pintype "passive"))
      (node (ref "U3") (pin "11") (pinfunction "V–_11") (pintype "passive"))
    )
    (net (code "40") (name "Net-(JP1-Pad2)") (class "Default")
      (node (ref "JP1") (pin "2") (pinfunction "2_2") (pintype "passive"))
      (node (ref "R16") (pin "2") (pinfunction "2_2") (pintype "passive"))
    )
    (net (code "41") (name "Net-(JP2-Pad2)") (class "Default")
      (node (ref "JP2") (pin "2") (pinfunction "2_2") (pintype "passive"))
      (node (ref "R17") (pin "2") (pinfunction "2_2") (pintype "passive"))
    )
    (net (code "42") (name "Net-(JP3-Pad2)") (class "Default")
      (node (ref "JP3") (pin "2") (pinfunction "2_2") (pintype "passive"))
      (node (ref "R18") (pin "2") (pinfunction "2_2") (pintype "passive"))
    )
    (net (code "43") (name "Net-(JP4-Pad2)") (class "Default")
      (node (ref "JP4") (pin "2") (pinfunction "2_2") (pintype "passive"))
      (node (ref "R34") (pin "2") (pinfunction "2_2") (pintype "passive"))
    )
    (net (code "44") (name "Net-(JP5-Pad2)") (class "Default")
      (node (ref "JP5") (pin "2") (pinfunction "2_2") (pintype "passive"))
      (node (ref "R35") (pin "2") (pinfunction "2_2") (pintype "passive"))
    )
    (net (code "45") (name "Net-(JP6-Pad2)") (class "Default")
      (node (ref "JP6") (pin "2") (pinfunction "2_2") (pintype "passive"))
      (node (ref "R36") (pin "2") (pinfunction "2_2") (pintype "passive"))
    )
    (net (code "46") (name "Net-(JP7-Pad2)") (class "Default")
      (node (ref "JP7") (pin "2") (pinfunction "2_2") (pintype "passive"))
      (node (ref "R52") (pin "2") (pinfunction "2_2") (pintype "passive"))
    )
    (net (code "47") (name "Net-(JP8-Pad2)") (class "Default")
      (node (ref "JP8") (pin "2") (pinfunction "2_2") (pintype "passive"))
      (node (ref "R53") (pin "2") (pinfunction "2_2") (pintype "passive"))
    )
    (net (code "48") (name "Net-(JP9-Pad2)") (class "Default")
      (node (ref "JP9") (pin "2") (pinfunction "2_2") (pintype "passive"))
      (node (ref "R54") (pin "2") (pinfunction "2_2") (pintype "passive"))
    )
    (net (code "49") (name "Net-(JP10-Pad2)") (class "Default")
      (node (ref "JP10") (pin "2") (pinfunction "2_2") (pintype "passive"))
      (node (ref "R70") (pin "2") (pinfunction "2_2") (pintype "passive"))
    )
    (net (code "50") (name "Net-(JP11-Pad2)") (class "Default")
      (node (ref "JP11") (pin "2") (pinfunction "2_2") (pintype "passive"))
      (node (ref "R71") (pin "2") (pinfunction "2_2") (pintype "passive"))
    )
    (net (code "51") (name "Net-(JP12-Pad2)") (class "Default")
      (node (ref "JP12") (pin "2") (pinfunction "2_2") (pintype "passive"))
      (node (ref "R72") (pin "2") (pinfunction "2_2") (pintype "passive"))
    )
    (net (code "52") (name "Net-(U1A-+)") (class "Default")
      (node (ref "C8") (pin "2") (pinfunction "2_2") (pintype "passive"))
      (node (ref "R12") (pin "2") (pinfunction "2_2") (pintype "passive"))
      (node (ref "R17") (pin "1") (pinfunction "1_1") (pintype "passive"))
      (node (ref "U1") (pin "3") (pinfunction "+_3") (pintype "passive"))
    )
    (net (code "53") (name "Net-(U1A-OUT)") (class "Default")
      (node (ref "C3") (pin "1") (pinfunction "1_1") (pintype "passive"))
      (node (ref "R9") (pin "1") (pinfunction "1_1") (pintype "passive"))
      (node (ref "U1") (pin "1") (pinfunction "OUT_1") (pintype "passive"))
    )
    (net (code "54") (name "Net-(U1A-–)") (class "Default")
      (node (ref "C3") (pin "2") (pinfunction "2_2") (pintype "passive"))
      (node (ref "R3") (pin "1") (pinfunction "1_1") (pintype "passive"))
      (node (ref "R6") (pin "2") (pinfunction "2_2") (pintype "passive"))
      (node (ref "U1") (pin "2") (pinfunction "–_2") (pintype "passive"))
    )
    (net (code "55") (name "Net-(U1B-+)") (class "Default")
      (node (ref "C17") (pin "2") (pinfunction "2_2") (pintype "passive"))
      (node (ref "R30") (pin "2") (pinfunction "2_2") (pintype "passive"))
      (node (ref "R35") (pin "1") (pinfunction "1_1") (pintype "passive"))
      (node (ref "U1") (pin "5") (pinfunction "+_5") (pintype "passive"))
    )
    (net (code "56") (name "Net-(U1B-OUT)") (class "Default")
      (node (ref "C12") (pin "1") (pinfunction "1_1") (pintype "passive"))
      (node (ref "R27") (pin "1") (pinfunction "1_1") (pintype "passive"))
      (node (ref "U1") (pin "7") (pinfunction "OUT_7") (pintype "passive"))
    )
    (net (code "57") (name "Net-(U1B-–)") (class "Default")
      (node (ref "C12") (pin "2") (pinfunction "2_2") (pintype "passive"))
      (node (ref "R21") (pin "1") (pinfunction "1_1") (pintype "passive"))
      (node (ref "R24") (pin "2") (pinfunction "2_2") (pintype "passive"))
      (node (ref "U1") (pin "6") (pinfunction "–_6") (pintype "passive"))
    )
    (net (code "58") (name "Net-(U1C-+)") (class "Default")
      (node (ref "C16") (pin "2") (pinfunction "2_2") (pintype "passive"))
      (node (ref "R28") (pin "2") (pinfunction "2_2") (pintype "passive"))
      (node (ref "R34") (pin "1") (pinfunction "1_1") (pintype "passive"))
      (node (ref "U1") (pin "10") (pinfunction "+_10") (pintype "passive"))
    )
    (net (code "59") (name "Net-(U1C-OUT)") (class "Default")
      (node (ref "C10") (pin "1") (pinfunction "1_1") (pintype "passive"))
      (node (ref "R25") (pin "1") (pinfunction "1_1") (pintype "passive"))
      (node (ref "U1") (pin "8") (pinfunction "OUT_8") (pintype "passive"))
    )
    (net (code "60") (name "Net-(U1C-–)") (class "Default")
      (node (ref "C10") (pin "2") (pinfunction "2_2") (pintype "passive"))
      (node (ref "R19") (pin "1") (pinfunction "1_1") (pintype "passive"))
      (node (ref "R22") (pin "2") (pinfunction "2_2") (pintype "passive"))
      (node (ref "U1") (pin "9") (pinfunction "–_9") (pintype "passive"))
    )
    (net (code "61") (name "Net-(U1D-+)") (class "Default")
      (node (ref "C7") (pin "2") (pinfunction "2_2") (pintype "passive"))
      (node (ref "R10") (pin "2") (pinfunction "2_2") (pintype "passive"))
      (node (ref "R16") (pin "1") (pinfunction "1_1") (pintype "passive"))
      (node (ref "U1") (pin "12") (pinfunction "+_12") (pintype "passive"))
    )
    (net (code "62") (name "Net-(U1D-OUT)") (class "Default")
      (node (ref "C1") (pin "1") (pinfunction "1_1") (pintype "passive"))
      (node (ref "R7") (pin "1") (pinfunction "1_1") (pintype "passive"))
      (node (ref "U1") (pin "14") (pinfunction "OUT_14") (pintype "passive"))
    )
    (net (code "63") (name "Net-(U1D-–)") (class "Default")
      (node (ref "C1") (pin "2") (pinfunction "2_2") (pintype "passive"))
      (node (ref "R1") (pin "1") (pinfunction "1_1") (pintype "passive"))
      (node (ref "R4") (pin "2") (pinfunction "2_2") (pintype "passive"))
      (node (ref "U1") (pin "13") (pinfunction "–_13") (pintype "passive"))
    )
    (net (code "64") (name "Net-(U2A-+)") (class "Default")
      (node (ref "C26") (pin "2") (pinfunction "2_2") (pintype "passive"))
      (node (ref "R47") (pin "2") (pinfunction "2_2") (pintype "passive"))
      (node (ref "R53") (pin "1") (pinfunction "1_1") (pintype "passive"))
      (node (ref "U2") (pin "3") (pinfunction "+_3") (pintype "passive"))
    )
    (net (code "65") (name "Net-(U2A-OUT)") (class "Default")
      (node (ref "C20") (pin "1") (pinfunction "1_1") (pintype "passive"))
      (node (ref "R44") (pin "1") (pinfunction "1_1") (pintype "passive"))
      (node (ref "U2") (pin "1") (pinfunction "OUT_1") (pintype "passive"))
    )
    (net (code "66") (name "Net-(U2A-–)") (class "Default")
      (node (ref "C20") (pin "2") (pinfunction "2_2") (pintype "passive"))
      (node (ref "R38") (pin "1") (pinfunction "1_1") (pintype "passive"))
      (node (ref "R41") (pin "2") (pinfunction "2_2") (pintype "passive"))
      (node (ref "U2") (pin "2") (pinfunction "–_2") (pintype "passive"))
    )
    (net (code "67") (name "Net-(U2B-+)") (class "Default")
      (node (ref "C36") (pin "2") (pinfunction "2_2") (pintype "passive"))
      (node (ref "R65") (pin "2") (pinfunction "2_2") (pintype "passive"))
      (node (ref "R72") (pin "1") (pinfunction "1_1") (pintype "passive"))
      (node (ref "U2") (pin "5") (pinfunction "+_5") (pintype "passive"))
    )
    (net (code "68") (name "Net-(U2B-OUT)") (class "Default")
      (node (ref "C29") (pin "1") (pinfunction "1_1") (pintype "passive"))
      (node (ref "R62") (pin "1") (pinfunction "1_1") (pintype "passive"))
      (node (ref "U2") (pin "7") (pinfunction "OUT_7") (pintype "passive"))
    )
    (net (code "69") (name "Net-(U2B-–)") (class "Default")
      (node (ref "C29") (pin "2") (pinfunction "2_2") (pintype "passive"))
      (node (ref "R56") (pin "1") (pinfunction "1_1") (pintype "passive"))
      (node (ref "R59") (pin "2") (pinfunction "2_2") (pintype "passive"))
      (node (ref "U2") (pin "6") (pinfunction "–_6") (pintype "passive"))
    )
    (net (code "70") (name "Net-(U2C-+)") (class "Default")
      (node (ref "C18") (pin "2") (pinfunction "2_2") (pintype "passive"))
      (node (ref "R29") (pin "2") (pinfunction "2_2") (pintype "passive"))
      (node (ref "R36") (pin "1") (pinfunction "1_1") (pintype "passive"))
      (node (ref "U2") (pin "10") (pinfunction "+_10") (pintype "passive"))
    )
    (net (code "71") (name "Net-(U2C-OUT)") (class "Default")
      (node (ref "C11") (pin "1") (pinfunction "1_1") (pintype "passive"))
      (node (ref "R26") (pin "1") (pinfunction "1_1") (pintype "passive"))
      (node (ref "U2") (pin "8") (pinfunction "OUT_8") (pintype "passive"))
    )
    (net (code "72") (name "Net-(U2C-–)") (class "Default")
      (node (ref "C11") (pin "2") (pinfunction "2_2") (pintype "passive"))
      (node (ref "R20") (pin "1") (pinfunction "1_1") (pintype "passive"))
      (node (ref "R23") (pin "2") (pinfunction "2_2") (pintype "passive"))
      (node (ref "U2") (pin "9") (pinfunction "–_9") (pintype "passive"))
    )
    (net (code "73") (name "Net-(U2D-+)") (class "Default")
      (node (ref "C9") (pin "2") (pinfunction "2_2") (pintype "passive"))
      (node (ref "R11") (pin "2") (pinfunction "2_2") (pintype "passive"))
      (node (ref "R18") (pin "1") (pinfunction "1_1") (pintype "passive"))
      (node (ref "U2") (pin "12") (pinfunction "+_12") (pintype "passive"))
    )
    (net (code "74") (name "Net-(U2D-OUT)") (class "Default")
      (node (ref "C2") (pin "1") (pinfunction "1_1") (pintype "passive"))
      (node (ref "R8") (pin "1") (pinfunction "1_1") (pintype "passive"))
      (node (ref "U2") (pin "14") (pinfunction "OUT_14") (pintype "passive"))
    )
    (net (code "75") (name "Net-(U2D-–)") (class "Default")
      (node (ref "C2") (pin "2") (pinfunction "2_2") (pintype "passive"))
      (node (ref "R2") (pin "1") (pinfunction "1_1") (pintype "passive"))
      (node (ref "R5") (pin "2") (pinfunction "2_2") (pintype "passive"))
      (node (ref "U2") (pin "13") (pinfunction "–_13") (pintype "passive"))
    )
    (net (code "76") (name "Net-(U3A-+)") (class "Default")
      (node (ref "C27") (pin "2") (pinfunction "2_2") (pintype "passive"))
      (node (ref "R48") (pin "2") (pinfunction "2_2") (pintype "passive"))
      (node (ref "R54") (pin "1") (pinfunction "1_1") (pintype "passive"))
      (node (ref "U3") (pin "3") (pinfunction "+_3") (pintype "passive"))
    )
    (net (code "77") (name "Net-(U3A-OUT)") (class "Default")
      (node (ref "C21") (pin "1") (pinfunction "1_1") (pintype "passive"))
      (node (ref "R45") (pin "1") (pinfunction "1_1") (pintype "passive"))
      (node (ref "U3") (pin "1") (pinfunction "OUT_1") (pintype "passive"))
    )
    (net (code "78") (name "Net-(U3A-–)") (class "Default")
      (node (ref "C21") (pin "2") (pinfunction "2_2") (pintype "passive"))
      (node (ref "R39") (pin "1") (pinfunction "1_1") (pintype "passive"))
      (node (ref "R42") (pin "2") (pinfunction "2_2") (pintype "passive"))
      (node (ref "U3") (pin "2") (pinfunction "–_2") (pintype "passive"))
    )
    (net (code "79") (name "Net-(U3B-+)") (class "Default")
      (node (ref "C35") (pin "2") (pinfunction "2_2") (pintype "passive"))
      (node (ref "R66") (pin "2") (pinfunction "2_2") (pintype "passive"))
      (node (ref "R71") (pin "1") (pinfunction "1_1") (pintype "passive"))
      (node (ref "U3") (pin "5") (pinfunction "+_5") (pintype "passive"))
    )
    (net (code "80") (name "Net-(U3B-OUT)") (class "Default")
      (node (ref "C30") (pin "1") (pinfunction "1_1") (pintype "passive"))
      (node (ref "R63") (pin "1") (pinfunction "1_1") (pintype "passive"))
      (node (ref "U3") (pin "7") (pinfunction "OUT_7") (pintype "passive"))
    )
    (net (code "81") (name "Net-(U3B-–)") (class "Default")
      (node (ref "C30") (pin "2") (pinfunction "2_2") (pintype "passive"))
      (node (ref "R57") (pin "1") (pinfunction "1_1") (pintype "passive"))
      (node (ref "R60") (pin "2") (pinfunction "2_2") (pintype "passive"))
      (node (ref "U3") (pin "6") (pinfunction "–_6") (pintype "passive"))
    )
    (net (code "82") (name "Net-(U3C-+)") (class "Default")
      (node (ref "C34") (pin "2") (pinfunction "2_2") (pintype "passive"))
      (node (ref "R64") (pin "2") (pinfunction "2_2") (pintype "passive"))
      (node (ref "R70") (pin "1") (pinfunction "1_1") (pintype "passive"))
      (node (ref "U3") (pin "10") (pinfunction "+_10") (pintype "passive"))
    )
    (net (code "83") (name "Net-(U3C-OUT)") (class "Default")
      (node (ref "C28") (pin "1") (pinfunction "1_1") (pintype "passive"))
      (node (ref "R61") (pin "1") (pinfunction "1_1") (pintype "passive"))
      (node (ref "U3") (pin "8") (pinfunction "OUT_8") (pintype "passive"))
    )
    (net (code "84") (name "Net-(U3C-–)") (class "Default")
      (node (ref "C28") (pin "2") (pinfunction "2_2") (pintype "passive"))
      (node (ref "R55") (pin "1") (pinfunction "1_1") (pintype "passive"))
      (node (ref "R58") (pin "2") (pinfunction "2_2") (pintype "passive"))
      (node (ref "U3") (pin "9") (pinfunction "–_9") (pintype "passive"))
    )
    (net (code "85") (name "Net-(U3D-+)") (class "Default")
      (node (ref "C25") (pin "2") (pinfunction "2_2") (pintype "passive"))
      (node (ref "R46") (pin "2") (pinfunction "2_2") (pintype "passive"))
      (node (ref "R52") (pin "1") (pinfunction "1_1") (pintype "passive"))
      (node (ref "U3") (pin "12") (pinfunction "+_12") (pintype "passive"))
    )
    (net (code "86") (name "Net-(U3D-OUT)") (class "Default")
      (node (ref "C19") (pin "1") (pinfunction "1_1") (pintype "passive"))
      (node (ref "R43") (pin "1") (pinfunction "1_1") (pintype "passive"))
      (node (ref "U3") (pin "14") (pinfunction "OUT_14") (pintype "passive"))
    )
    (net (code "87") (name "Net-(U3D-–)") (class "Default")
      (node (ref "C19") (pin "2") (pinfunction "2_2") (pintype "passive"))
      (node (ref "R37") (pin "1") (pinfunction "1_1") (pintype "passive"))
      (node (ref "R40") (pin "2") (pinfunction "2_2") (pintype "passive"))
      (node (ref "U3") (pin "13") (pinfunction "–_13") (pintype "passive"))
    )
  )
)
